# LinkLite.net
KiCad netlist of a schematic drawn in Altium Designer
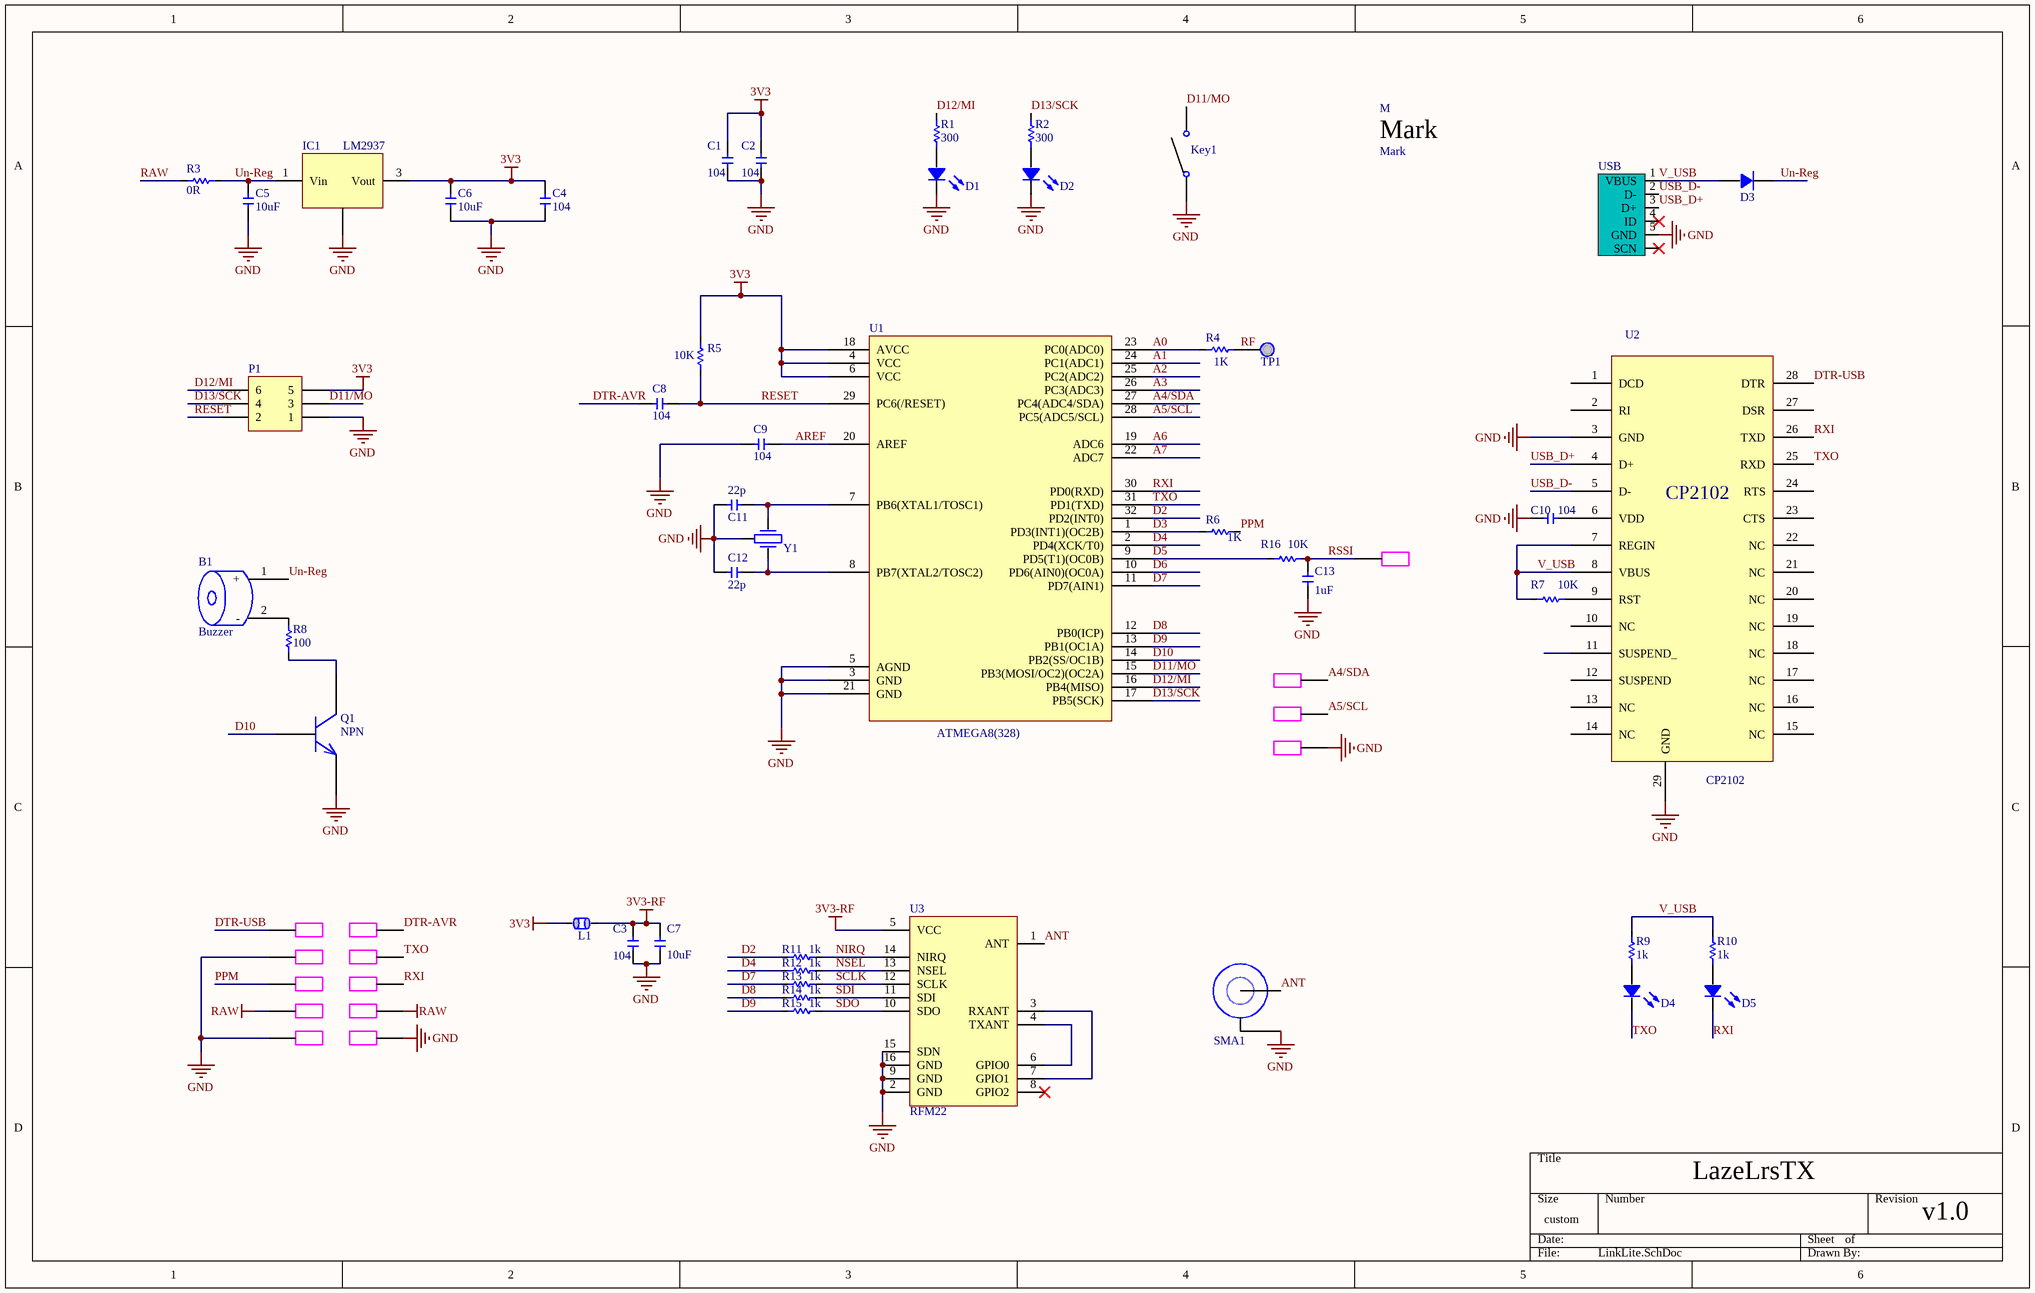
[diagram p0: LinkLite.SchDoc]

(export (version "E")
  (design (tool "Eeschema 10.0.6"))
  (components
    (comp (ref "B1") (value "Buzzer") (footprint "BUZZER9055") (libsource (lib "Drone") (part "Buzzer")))
    (comp (ref "C1")
      (value "104")
      (footprint "0603 CAP")
      (description "Capacitor")
      (fields (field (name "PUBLISHER") "Altium Limited"))
      (libsource (lib "Drone") (part "CAP"))
    )
    (comp (ref "C2")
      (value "104")
      (footprint "0603 CAP")
      (description "Capacitor")
      (fields (field (name "PUBLISHER") "Altium Limited"))
      (libsource (lib "Drone") (part "CAP"))
    )
    (comp (ref "C3")
      (value "104")
      (footprint "0603 CAP")
      (description "Capacitor")
      (fields (field (name "PUBLISHER") "Altium Limited"))
      (libsource (lib "Drone") (part "CAP"))
    )
    (comp (ref "C4")
      (value "104")
      (footprint "0603 CAP")
      (description "Capacitor")
      (fields (field (name "PUBLISHER") "Altium Limited"))
      (libsource (lib "Drone") (part "CAP"))
    )
    (comp (ref "C5")
      (value "10uF")
      (footprint "1206")
      (description "Capacitor")
      (fields (field (name "PUBLISHER") "Altium Limited"))
      (libsource (lib "Drone") (part "CAP"))
    )
    (comp (ref "C6")
      (value "10uF")
      (footprint "1206")
      (description "Capacitor")
      (fields (field (name "PUBLISHER") "Altium Limited"))
      (libsource (lib "Drone") (part "CAP"))
    )
    (comp (ref "C7")
      (value "10uF")
      (footprint "1206")
      (description "Capacitor")
      (fields (field (name "PUBLISHER") "Altium Limited"))
      (libsource (lib "Drone") (part "CAP"))
    )
    (comp (ref "C8")
      (value "104")
      (footprint "0603 CAP")
      (description "Capacitor")
      (fields (field (name "PUBLISHER") "Altium Limited"))
      (libsource (lib "Drone") (part "CAP"))
    )
    (comp (ref "C9")
      (value "104")
      (footprint "0603 CAP")
      (description "Capacitor")
      (fields (field (name "PUBLISHER") "Altium Limited"))
      (libsource (lib "Drone") (part "CAP"))
    )
    (comp (ref "C10")
      (value "104")
      (footprint "0603 CAP")
      (description "Capacitor")
      (fields (field (name "PUBLISHER") "Altium Limited"))
      (libsource (lib "Drone") (part "CAP"))
    )
    (comp (ref "C11")
      (value "22p")
      (footprint "0603 CAP")
      (description "Capacitor")
      (fields (field (name "PUBLISHER") "Altium Limited"))
      (libsource (lib "Drone") (part "CAP"))
    )
    (comp (ref "C12")
      (value "22p")
      (footprint "0603 CAP")
      (description "Capacitor")
      (fields (field (name "PUBLISHER") "Altium Limited"))
      (libsource (lib "Drone") (part "CAP"))
    )
    (comp (ref "C13")
      (value "1uF")
      (footprint "0603 CAP")
      (description "Capacitor")
      (fields (field (name "PUBLISHER") "Altium Limited"))
      (libsource (lib "Drone") (part "CAP"))
    )
    (comp (ref "D1")
      (value "LED")
      (footprint "0805 LED")
      (description "Typical RED, GREEN, YELLOW, AMBER GaAs LED")
      (fields (field (name "PUBLISHER") "Altium Limited"))
      (libsource (lib "Drone") (part "LED"))
    )
    (comp (ref "D2")
      (value "LED")
      (footprint "0805 LED")
      (description "Typical RED, GREEN, YELLOW, AMBER GaAs LED")
      (fields (field (name "PUBLISHER") "Altium Limited"))
      (libsource (lib "Drone") (part "LED"))
    )
    (comp (ref "D3") (value "Diode") (footprint "DIODE-SOD123") (libsource (lib "Drone") (part "Diode")))
    (comp (ref "D4")
      (value "LED")
      (footprint "0603 cap")
      (description "Typical RED, GREEN, YELLOW, AMBER GaAs LED")
      (fields (field (name "PUBLISHER") "Altium Limited"))
      (libsource (lib "Drone") (part "LED"))
    )
    (comp (ref "D5")
      (value "LED")
      (footprint "0603 cap")
      (description "Typical RED, GREEN, YELLOW, AMBER GaAs LED")
      (fields (field (name "PUBLISHER") "Altium Limited"))
      (libsource (lib "Drone") (part "LED"))
    )
    (comp (ref "IC1") (value "LM2937") (footprint "LM2937") (libsource (lib "Drone") (part "LM2937")))
    (comp (ref "Key1") (value "Key666") (footprint "KEY 666") (libsource (lib "Drone") (part "Key666")))
    (comp (ref "L1")
      (value "FB 300mA")
      (footprint "0603 IND")
      (description "Ferrite Bead 300mA")
      (fields (field (name "MANUFACTURER") "Generic Components"))
      (libsource (lib "Drone") (part "FerriteBead_300mA"))
    )
    (comp (ref "M") (value "Mark") (footprint "MarkPoint") (libsource (lib "Drone") (part "Mark")))
    (comp (ref "P1")
      (value "Header 3X2")
      (footprint "HDR2X3")
      (description "Header, 3-Pin, Dual row")
      (fields (field (name "PUBLISHER") "Altium Limited"))
      (libsource (lib "Miscellaneous Connectors") (part "Header 3X2"))
    )
    (comp (ref "Pad1") (value "EdgePad") (footprint "edgepad") (libsource (lib "") (part "EdgePad_1")))
    (comp (ref "Pad2") (value "EdgePad") (footprint "edgepad") (libsource (lib "Drone") (part "EdgePad")))
    (comp (ref "Pad3") (value "EdgePad") (footprint "edgepad") (libsource (lib "") (part "EdgePad_1")))
    (comp (ref "Pad4") (value "EdgePad") (footprint "edgepad") (libsource (lib "Drone") (part "EdgePad")))
    (comp (ref "Pad5") (value "EdgePad") (footprint "edgepad") (libsource (lib "") (part "EdgePad_1")))
    (comp (ref "Pad6") (value "EdgePad") (footprint "edgepad") (libsource (lib "Drone") (part "EdgePad")))
    (comp (ref "Pad7") (value "EdgePad") (footprint "edgepad") (libsource (lib "") (part "EdgePad_1")))
    (comp (ref "Pad8") (value "EdgePad") (footprint "edgepad") (libsource (lib "Drone") (part "EdgePad")))
    (comp (ref "Pad9") (value "EdgePad") (footprint "edgepad") (libsource (lib "") (part "EdgePad_1")))
    (comp (ref "Pad10") (value "EdgePad") (footprint "edgepad") (libsource (lib "Drone") (part "EdgePad")))
    (comp (ref "Pad11") (value "EdgePad") (footprint "edgepad") (libsource (lib "Drone") (part "EdgePad")))
    (comp (ref "Pad12") (value "EdgePad") (footprint "edgepad") (libsource (lib "Drone") (part "EdgePad")))
    (comp (ref "Pad13") (value "EdgePad") (footprint "edgepad") (libsource (lib "") (part "EdgePad_1")))
    (comp (ref "Pad14") (value "EdgePad") (footprint "edgepad") (libsource (lib "Drone") (part "EdgePad")))
    (comp (ref "Q1") (value "NPN") (footprint "NPN-SOT-23B_M") (libsource (lib "Drone") (part "NPN")))
    (comp (ref "R1")
      (value "300")
      (footprint "0603 RES")
      (description "Resistor")
      (fields (field (name "PUBLISHER") "Altium Limited"))
      (libsource (lib "Drone") (part "Res"))
    )
    (comp (ref "R2")
      (value "300")
      (footprint "0603 RES")
      (description "Resistor")
      (fields (field (name "PUBLISHER") "Altium Limited"))
      (libsource (lib "Drone") (part "Res"))
    )
    (comp (ref "R3")
      (value "0R")
      (footprint "0603 RES")
      (description "Resistor")
      (fields (field (name "PUBLISHER") "Altium Limited"))
      (libsource (lib "Drone") (part "Res"))
    )
    (comp (ref "R4")
      (value "1K")
      (footprint "0603 RES")
      (description "Resistor")
      (fields (field (name "PUBLISHER") "Altium Limited"))
      (libsource (lib "Drone") (part "Res"))
    )
    (comp (ref "R5")
      (value "10K")
      (footprint "0603 RES")
      (description "Resistor")
      (fields (field (name "PUBLISHER") "Altium Limited"))
      (libsource (lib "Drone") (part "Res"))
    )
    (comp (ref "R6")
      (value "1K")
      (footprint "0603 RES")
      (description "Resistor")
      (fields (field (name "PUBLISHER") "Altium Limited"))
      (libsource (lib "Drone") (part "Res"))
    )
    (comp (ref "R7")
      (value "10K")
      (footprint "0603 RES")
      (description "Resistor")
      (fields (field (name "PUBLISHER") "Altium Limited"))
      (libsource (lib "Drone") (part "Res"))
    )
    (comp (ref "R8")
      (value "100")
      (footprint "0603 RES")
      (description "Resistor")
      (fields (field (name "PUBLISHER") "Altium Limited"))
      (libsource (lib "Drone") (part "Res"))
    )
    (comp (ref "R9")
      (value "1k")
      (footprint "0603 RES")
      (description "Resistor")
      (fields (field (name "PUBLISHER") "Altium Limited"))
      (libsource (lib "Drone") (part "Res"))
    )
    (comp (ref "R10")
      (value "1k")
      (footprint "0603 RES")
      (description "Resistor")
      (fields (field (name "PUBLISHER") "Altium Limited"))
      (libsource (lib "Drone") (part "Res"))
    )
    (comp (ref "R11")
      (value "1k")
      (footprint "0603 RES")
      (description "Resistor")
      (fields (field (name "PUBLISHER") "Altium Limited"))
      (libsource (lib "Drone") (part "Res"))
    )
    (comp (ref "R12")
      (value "1k")
      (footprint "0603 RES")
      (description "Resistor")
      (fields (field (name "PUBLISHER") "Altium Limited"))
      (libsource (lib "Drone") (part "Res"))
    )
    (comp (ref "R13")
      (value "1k")
      (footprint "0603 RES")
      (description "Resistor")
      (fields (field (name "PUBLISHER") "Altium Limited"))
      (libsource (lib "Drone") (part "Res"))
    )
    (comp (ref "R14")
      (value "1k")
      (footprint "0603 RES")
      (description "Resistor")
      (fields (field (name "PUBLISHER") "Altium Limited"))
      (libsource (lib "Drone") (part "Res"))
    )
    (comp (ref "R15")
      (value "1k")
      (footprint "0603 RES")
      (description "Resistor")
      (fields (field (name "PUBLISHER") "Altium Limited"))
      (libsource (lib "Drone") (part "Res"))
    )
    (comp (ref "R16")
      (value "10K")
      (footprint "0603 RES")
      (description "Resistor")
      (fields (field (name "PUBLISHER") "Altium Limited"))
      (libsource (lib "Drone") (part "Res"))
    )
    (comp (ref "SMA1") (value "SMA Base") (footprint "ANT SMA") (libsource (lib "Drone") (part "SMA Base")))
    (comp (ref "TP1")
      (value "Test Pad")
      (footprint "Test Pad 1.2MM")
      (libsource (lib "Drone") (part "Test Pad"))
    )
    (comp (ref "U1")
      (value "ATmega328")
      (footprint "ATMEGA328FIX")
      (libsource (lib "Drone") (part "ATmega328"))
    )
    (comp (ref "U2") (value "CP2102") (footprint "CP2102") (libsource (lib "Drone") (part "CP2102")))
    (comp (ref "U3") (value "RFM22") (footprint "RFM22SMD") (libsource (lib "Drone") (part "RFM22")))
    (comp (ref "USB")
      (value "USB")
      (footprint "MINI USB A")
      (description "USB Type-B SMT Socket")
      (libsource (lib "Drone") (part "USB_SMT_B"))
    )
    (comp (ref "Y1")
      (value "Crystal3Foot")
      (footprint "Crystal3Foot")
      (libsource (lib "Drone") (part "Crystal3Foot"))
    )
  )
  (nets
    (net (code "1") (name "/A0") (class "Default")
      (node (ref "R4") (pin "2") (pinfunction "2_2") (pintype "passive"))
      (node (ref "U1") (pin "23") (pinfunction "PC0(ADC0)_23") (pintype "passive"))
    )
    (net (code "2") (name "/A1") (class "Default")
      (node (ref "U1") (pin "24") (pinfunction "PC1(ADC1)_24") (pintype "passive"))
    )
    (net (code "3") (name "/A2") (class "Default")
      (node (ref "U1") (pin "25") (pinfunction "PC2(ADC2)_25") (pintype "passive"))
    )
    (net (code "4") (name "/A3") (class "Default")
      (node (ref "U1") (pin "26") (pinfunction "PC3(ADC3)_26") (pintype "passive"))
    )
    (net (code "5") (name "/A4{slash}SDA") (class "Default")
      (node (ref "Pad10") (pin "1") (pinfunction "1_1") (pintype "passive"))
      (node (ref "U1") (pin "27") (pinfunction "PC4(ADC4/SDA)_27") (pintype "passive"))
    )
    (net (code "6") (name "/A5{slash}SCL") (class "Default")
      (node (ref "Pad11") (pin "1") (pinfunction "1_1") (pintype "passive"))
      (node (ref "U1") (pin "28") (pinfunction "PC5(ADC5/SCL)_28") (pintype "passive"))
    )
    (net (code "7") (name "/A6") (class "Default")
      (node (ref "U1") (pin "19") (pinfunction "ADC6_19") (pintype "passive"))
    )
    (net (code "8") (name "/A7") (class "Default")
      (node (ref "U1") (pin "22") (pinfunction "ADC7_22") (pintype "passive"))
    )
    (net (code "9") (name "/ANT") (class "Default")
      (node (ref "SMA1") (pin "1") (pinfunction "Ant_1") (pintype "passive"))
      (node (ref "U3") (pin "1") (pinfunction "ANT_1") (pintype "passive"))
    )
    (net (code "10") (name "/AREF") (class "Default")
      (node (ref "C9") (pin "1") (pinfunction "1_1") (pintype "passive"))
      (node (ref "U1") (pin "20") (pinfunction "AREF_20") (pintype "passive"))
    )
    (net (code "11") (name "/D2") (class "Default")
      (node (ref "R11") (pin "2") (pinfunction "2_2") (pintype "passive"))
      (node (ref "U1") (pin "32") (pinfunction "PD2(INT0)_32") (pintype "passive"))
    )
    (net (code "12") (name "/D3") (class "Default")
      (node (ref "R6") (pin "2") (pinfunction "2_2") (pintype "passive"))
      (node (ref "U1") (pin "1") (pinfunction "PD3(INT1)(OC2B)_1") (pintype "passive"))
    )
    (net (code "13") (name "/D4") (class "Default")
      (node (ref "R12") (pin "2") (pinfunction "2_2") (pintype "passive"))
      (node (ref "U1") (pin "2") (pinfunction "PD4(XCK/T0)_2") (pintype "passive"))
    )
    (net (code "14") (name "/D5") (class "Default")
      (node (ref "R16") (pin "2") (pinfunction "2_2") (pintype "passive"))
      (node (ref "U1") (pin "9") (pinfunction "PD5(T1)(OC0B)_9") (pintype "passive"))
    )
    (net (code "15") (name "/D6") (class "Default")
      (node (ref "U1") (pin "10") (pinfunction "PD6(AIN0)(OC0A)_10") (pintype "passive"))
    )
    (net (code "16") (name "/D7") (class "Default")
      (node (ref "R13") (pin "2") (pinfunction "2_2") (pintype "passive"))
      (node (ref "U1") (pin "11") (pinfunction "PD7(AIN1)_11") (pintype "passive"))
    )
    (net (code "17") (name "/D8") (class "Default")
      (node (ref "R14") (pin "2") (pinfunction "2_2") (pintype "passive"))
      (node (ref "U1") (pin "12") (pinfunction "PB0(ICP)_12") (pintype "passive"))
    )
    (net (code "18") (name "/D9") (class "Default")
      (node (ref "R15") (pin "2") (pinfunction "2_2") (pintype "passive"))
      (node (ref "U1") (pin "13") (pinfunction "PB1(OC1A)_13") (pintype "passive"))
    )
    (net (code "19") (name "/D10") (class "Default")
      (node (ref "Q1") (pin "1") (pinfunction "Sig_1") (pintype "passive"))
      (node (ref "U1") (pin "14") (pinfunction "PB2(SS/OC1B)_14") (pintype "passive"))
    )
    (net (code "20") (name "/D11{slash}MO") (class "Default")
      (node (ref "Key1") (pin "2") (pinfunction "2_2") (pintype "passive"))
      (node (ref "P1") (pin "3") (pinfunction "3_3") (pintype "passive"))
      (node (ref "U1") (pin "15") (pinfunction "PB3(MOSI/OC2)(OC2A)_15") (pintype "passive"))
    )
    (net (code "21") (name "/D12{slash}MI") (class "Default")
      (node (ref "P1") (pin "6") (pinfunction "6_6") (pintype "passive"))
      (node (ref "R1") (pin "1") (pinfunction "1_1") (pintype "passive"))
      (node (ref "U1") (pin "16") (pinfunction "PB4(MISO)_16") (pintype "passive"))
    )
    (net (code "22") (name "/D13{slash}SCK") (class "Default")
      (node (ref "P1") (pin "4") (pinfunction "4_4") (pintype "passive"))
      (node (ref "R2") (pin "1") (pinfunction "1_1") (pintype "passive"))
      (node (ref "U1") (pin "17") (pinfunction "PB5(SCK)_17") (pintype "passive"))
    )
    (net (code "23") (name "/DTR-AVR") (class "Default")
      (node (ref "C8") (pin "2") (pinfunction "2_2") (pintype "passive"))
      (node (ref "Pad2") (pin "1") (pinfunction "1_1") (pintype "passive"))
    )
    (net (code "24") (name "/DTR-USB") (class "Default")
      (node (ref "Pad1") (pin "1") (pinfunction "1_1") (pintype "passive"))
      (node (ref "U2") (pin "28") (pinfunction "DTR_28") (pintype "passive"))
    )
    (net (code "25") (name "/NIRQ") (class "Default")
      (node (ref "R11") (pin "1") (pinfunction "1_1") (pintype "passive"))
      (node (ref "U3") (pin "14") (pinfunction "NIRQ_14") (pintype "passive"))
    )
    (net (code "26") (name "/NSEL") (class "Default")
      (node (ref "R12") (pin "1") (pinfunction "1_1") (pintype "passive"))
      (node (ref "U3") (pin "13") (pinfunction "NSEL_13") (pintype "passive"))
    )
    (net (code "27") (name "/PPM") (class "Default")
      (node (ref "Pad5") (pin "1") (pinfunction "1_1") (pintype "passive"))
      (node (ref "R6") (pin "1") (pinfunction "1_1") (pintype "passive"))
    )
    (net (code "28") (name "/RESET") (class "Default")
      (node (ref "C8") (pin "1") (pinfunction "1_1") (pintype "passive"))
      (node (ref "P1") (pin "2") (pinfunction "2_2") (pintype "passive"))
      (node (ref "R5") (pin "1") (pinfunction "1_1") (pintype "passive"))
      (node (ref "U1") (pin "29") (pinfunction "PC6(/RESET)_29") (pintype "passive"))
    )
    (net (code "29") (name "/RF") (class "Default")
      (node (ref "R4") (pin "1") (pinfunction "1_1") (pintype "passive"))
      (node (ref "TP1") (pin "1") (pinfunction "1_1") (pintype "passive"))
    )
    (net (code "30") (name "/RSSI") (class "Default")
      (node (ref "C13") (pin "2") (pinfunction "2_2") (pintype "passive"))
      (node (ref "Pad13") (pin "1") (pinfunction "1_1") (pintype "passive"))
      (node (ref "R16") (pin "1") (pinfunction "1_1") (pintype "passive"))
    )
    (net (code "31") (name "/RXI") (class "Default")
      (node (ref "D5") (pin "2") (pinfunction "K_2") (pintype "passive"))
      (node (ref "Pad6") (pin "1") (pinfunction "1_1") (pintype "passive"))
      (node (ref "U1") (pin "30") (pinfunction "PD0(RXD)_30") (pintype "passive"))
      (node (ref "U2") (pin "26") (pinfunction "TXD_26") (pintype "passive"))
    )
    (net (code "32") (name "/SCLK") (class "Default")
      (node (ref "R13") (pin "1") (pinfunction "1_1") (pintype "passive"))
      (node (ref "U3") (pin "12") (pinfunction "SCLK_12") (pintype "passive"))
    )
    (net (code "33") (name "/SDI") (class "Default")
      (node (ref "R14") (pin "1") (pinfunction "1_1") (pintype "passive"))
      (node (ref "U3") (pin "11") (pinfunction "SDI_11") (pintype "passive"))
    )
    (net (code "34") (name "/SDO") (class "Default")
      (node (ref "R15") (pin "1") (pinfunction "1_1") (pintype "passive"))
      (node (ref "U3") (pin "10") (pinfunction "SDO_10") (pintype "passive"))
    )
    (net (code "35") (name "/TXO") (class "Default")
      (node (ref "D4") (pin "2") (pinfunction "K_2") (pintype "passive"))
      (node (ref "Pad4") (pin "1") (pinfunction "1_1") (pintype "passive"))
      (node (ref "U1") (pin "31") (pinfunction "PD1(TXD)_31") (pintype "passive"))
      (node (ref "U2") (pin "25") (pinfunction "RXD_25") (pintype "passive"))
    )
    (net (code "36") (name "/USB_D+") (class "Default")
      (node (ref "U2") (pin "4") (pinfunction "D+_4") (pintype "passive"))
      (node (ref "USB") (pin "3") (pinfunction "D+_3") (pintype "passive"))
    )
    (net (code "37") (name "/USB_D-") (class "Default")
      (node (ref "U2") (pin "5") (pinfunction "D-_5") (pintype "passive"))
      (node (ref "USB") (pin "2") (pinfunction "D-_2") (pintype "passive"))
    )
    (net (code "38") (name "/Un-Reg") (class "Default")
      (node (ref "B1") (pin "1") (pinfunction "+_1") (pintype "passive"))
      (node (ref "C5") (pin "2") (pinfunction "2_2") (pintype "passive"))
      (node (ref "D3") (pin "2") (pinfunction "B_2") (pintype "passive"))
      (node (ref "IC1") (pin "1") (pinfunction "Vin_1") (pintype "passive"))
      (node (ref "R3") (pin "1") (pinfunction "1_1") (pintype "passive"))
    )
    (net (code "39") (name "/V_USB") (class "Default")
      (node (ref "D3") (pin "1") (pinfunction "A_1") (pintype "passive"))
      (node (ref "R10") (pin "1") (pinfunction "1_1") (pintype "passive"))
      (node (ref "R7") (pin "2") (pinfunction "2_2") (pintype "passive"))
      (node (ref "R9") (pin "1") (pinfunction "1_1") (pintype "passive"))
      (node (ref "U2") (pin "7") (pinfunction "REGIN_7") (pintype "passive"))
      (node (ref "U2") (pin "8") (pinfunction "VBUS_8") (pintype "passive"))
      (node (ref "USB") (pin "1") (pinfunction "VBUS_1") (pintype "passive"))
    )
    (net (code "40") (name "3V3") (class "Default")
      (node (ref "C1") (pin "1") (pinfunction "1_1") (pintype "passive"))
      (node (ref "C2") (pin "1") (pinfunction "1_1") (pintype "passive"))
      (node (ref "C4") (pin "1") (pinfunction "1_1") (pintype "passive"))
      (node (ref "C6") (pin "2") (pinfunction "2_2") (pintype "passive"))
      (node (ref "IC1") (pin "3") (pinfunction "Vout_3") (pintype "passive"))
      (node (ref "L1") (pin "1") (pinfunction "1_1") (pintype "passive"))
      (node (ref "P1") (pin "5") (pinfunction "5_5") (pintype "passive"))
      (node (ref "R5") (pin "2") (pinfunction "2_2") (pintype "passive"))
      (node (ref "U1") (pin "18") (pinfunction "AVCC_18") (pintype "passive"))
      (node (ref "U1") (pin "4") (pinfunction "VCC_4") (pintype "passive"))
      (node (ref "U1") (pin "6") (pinfunction "VCC_6") (pintype "passive"))
    )
    (net (code "41") (name "3V3-RF") (class "Default")
      (node (ref "C3") (pin "1") (pinfunction "1_1") (pintype "passive"))
      (node (ref "C7") (pin "1") (pinfunction "1_1") (pintype "passive"))
      (node (ref "L1") (pin "2") (pinfunction "2_2") (pintype "passive"))
      (node (ref "U3") (pin "5") (pinfunction "VCC_5") (pintype "passive"))
    )
    (net (code "42") (name "GND") (class "Default")
      (node (ref "C1") (pin "2") (pinfunction "2_2") (pintype "passive"))
      (node (ref "C10") (pin "1") (pinfunction "1_1") (pintype "passive"))
      (node (ref "C11") (pin "1") (pinfunction "1_1") (pintype "passive"))
      (node (ref "C12") (pin "1") (pinfunction "1_1") (pintype "passive"))
      (node (ref "C13") (pin "1") (pinfunction "1_1") (pintype "passive"))
      (node (ref "C2") (pin "2") (pinfunction "2_2") (pintype "passive"))
      (node (ref "C3") (pin "2") (pinfunction "2_2") (pintype "passive"))
      (node (ref "C4") (pin "2") (pinfunction "2_2") (pintype "passive"))
      (node (ref "C5") (pin "1") (pinfunction "1_1") (pintype "passive"))
      (node (ref "C6") (pin "1") (pinfunction "1_1") (pintype "passive"))
      (node (ref "C7") (pin "2") (pinfunction "2_2") (pintype "passive"))
      (node (ref "C9") (pin "2") (pinfunction "2_2") (pintype "passive"))
      (node (ref "D1") (pin "2") (pinfunction "K_2") (pintype "passive"))
      (node (ref "D2") (pin "2") (pinfunction "K_2") (pintype "passive"))
      (node (ref "IC1") (pin "2") (pinfunction "Gnd_2") (pintype "passive"))
      (node (ref "Key1") (pin "1") (pinfunction "1_1") (pintype "passive"))
      (node (ref "P1") (pin "1") (pinfunction "1_1") (pintype "passive"))
      (node (ref "Pad12") (pin "1") (pinfunction "1_1") (pintype "passive"))
      (node (ref "Pad14") (pin "1") (pinfunction "1_1") (pintype "passive"))
      (node (ref "Pad3") (pin "1") (pinfunction "1_1") (pintype "passive"))
      (node (ref "Pad9") (pin "1") (pinfunction "1_1") (pintype "passive"))
      (node (ref "Q1") (pin "2") (pinfunction "Gnd_2") (pintype "passive"))
      (node (ref "SMA1") (pin "2") (pinfunction "Gnd_2") (pintype "passive"))
      (node (ref "U1") (pin "21") (pinfunction "GND_21") (pintype "passive"))
      (node (ref "U1") (pin "3") (pinfunction "GND_3") (pintype "passive"))
      (node (ref "U1") (pin "5") (pinfunction "AGND_5") (pintype "passive"))
      (node (ref "U2") (pin "29") (pinfunction "GND_29") (pintype "passive"))
      (node (ref "U2") (pin "3") (pinfunction "GND_3") (pintype "passive"))
      (node (ref "U3") (pin "15") (pinfunction "SDN_15") (pintype "passive"))
      (node (ref "U3") (pin "16") (pinfunction "GND_16") (pintype "passive"))
      (node (ref "U3") (pin "2") (pinfunction "GND_2") (pintype "passive"))
      (node (ref "U3") (pin "9") (pinfunction "GND_9") (pintype "passive"))
      (node (ref "USB") (pin "5") (pinfunction "GND_5") (pintype "passive"))
      (node (ref "Y1") (pin "2") (pinfunction "2_2") (pintype "passive"))
    )
    (net (code "43") (name "Net-(B1--)") (class "Default")
      (node (ref "B1") (pin "2") (pinfunction "-_2") (pintype "passive"))
      (node (ref "R8") (pin "1") (pinfunction "1_1") (pintype "passive"))
    )
    (net (code "44") (name "Net-(D1-A)") (class "Default")
      (node (ref "D1") (pin "1") (pinfunction "A_1") (pintype "passive"))
      (node (ref "R1") (pin "2") (pinfunction "2_2") (pintype "passive"))
    )
    (net (code "45") (name "Net-(D2-A)") (class "Default")
      (node (ref "D2") (pin "1") (pinfunction "A_1") (pintype "passive"))
      (node (ref "R2") (pin "2") (pinfunction "2_2") (pintype "passive"))
    )
    (net (code "46") (name "Net-(D4-A)") (class "Default")
      (node (ref "D4") (pin "1") (pinfunction "A_1") (pintype "passive"))
      (node (ref "R9") (pin "2") (pinfunction "2_2") (pintype "passive"))
    )
    (net (code "47") (name "Net-(D5-A)") (class "Default")
      (node (ref "D5") (pin "1") (pinfunction "A_1") (pintype "passive"))
      (node (ref "R10") (pin "2") (pinfunction "2_2") (pintype "passive"))
    )
    (net (code "48") (name "Net-(Q1-Collector)") (class "Default")
      (node (ref "Q1") (pin "3") (pinfunction "Collector_3") (pintype "passive"))
      (node (ref "R8") (pin "2") (pinfunction "2_2") (pintype "passive"))
    )
    (net (code "49") (name "Net-(U1-PB6(XTAL1{slash}TOSC1))") (class "Default")
      (node (ref "C11") (pin "2") (pinfunction "2_2") (pintype "passive"))
      (node (ref "U1") (pin "7") (pinfunction "PB6(XTAL1/TOSC1)_7") (pintype "passive"))
      (node (ref "Y1") (pin "1") (pinfunction "0_1") (pintype "passive"))
    )
    (net (code "50") (name "Net-(U1-PB7(XTAL2{slash}TOSC2))") (class "Default")
      (node (ref "C12") (pin "2") (pinfunction "2_2") (pintype "passive"))
      (node (ref "U1") (pin "8") (pinfunction "PB7(XTAL2/TOSC2)_8") (pintype "passive"))
      (node (ref "Y1") (pin "3") (pinfunction "1_3") (pintype "passive"))
    )
    (net (code "51") (name "Net-(U2-RST)") (class "Default")
      (node (ref "R7") (pin "1") (pinfunction "1_1") (pintype "passive"))
      (node (ref "U2") (pin "9") (pinfunction "RST_9") (pintype "passive"))
    )
    (net (code "52") (name "Net-(U2-VDD)") (class "Default")
      (node (ref "C10") (pin "2") (pinfunction "2_2") (pintype "passive"))
      (node (ref "U2") (pin "6") (pinfunction "VDD_6") (pintype "passive"))
    )
    (net (code "53") (name "Net-(U3-GPIO0)") (class "Default")
      (node (ref "U3") (pin "4") (pinfunction "TXANT_4") (pintype "passive"))
      (node (ref "U3") (pin "6") (pinfunction "GPIO0_6") (pintype "passive"))
    )
    (net (code "54") (name "Net-(U3-GPIO1)") (class "Default")
      (node (ref "U3") (pin "3") (pinfunction "RXANT_3") (pintype "passive"))
      (node (ref "U3") (pin "7") (pinfunction "GPIO1_7") (pintype "passive"))
    )
    (net (code "55") (name "RAW") (class "Default")
      (node (ref "Pad7") (pin "1") (pinfunction "1_1") (pintype "passive"))
      (node (ref "Pad8") (pin "1") (pinfunction "1_1") (pintype "passive"))
      (node (ref "R3") (pin "2") (pinfunction "2_2") (pintype "passive"))
    )
    (net (code "56") (name "unconnected-(U2-CTS-Pad23)") (class "Default")
      (node (ref "U2") (pin "23") (pinfunction "CTS_23") (pintype "passive"))
    )
    (net (code "57") (name "unconnected-(U2-DCD-Pad1)") (class "Default")
      (node (ref "U2") (pin "1") (pinfunction "DCD_1") (pintype "passive"))
    )
    (net (code "58") (name "unconnected-(U2-DSR-Pad27)") (class "Default")
      (node (ref "U2") (pin "27") (pinfunction "DSR_27") (pintype "passive"))
    )
    (net (code "59") (name "unconnected-(U2-NC-Pad10)") (class "Default")
      (node (ref "U2") (pin "10") (pinfunction "NC_10") (pintype "passive"))
    )
    (net (code "60") (name "unconnected-(U2-NC-Pad13)") (class "Default")
      (node (ref "U2") (pin "13") (pinfunction "NC_13") (pintype "passive"))
    )
    (net (code "61") (name "unconnected-(U2-NC-Pad14)") (class "Default")
      (node (ref "U2") (pin "14") (pinfunction "NC_14") (pintype "passive"))
    )
    (net (code "62") (name "unconnected-(U2-NC-Pad15)") (class "Default")
      (node (ref "U2") (pin "15") (pinfunction "NC_15") (pintype "passive"))
    )
    (net (code "63") (name "unconnected-(U2-NC-Pad16)") (class "Default")
      (node (ref "U2") (pin "16") (pinfunction "NC_16") (pintype "passive"))
    )
    (net (code "64") (name "unconnected-(U2-NC-Pad17)") (class "Default")
      (node (ref "U2") (pin "17") (pinfunction "NC_17") (pintype "passive"))
    )
    (net (code "65") (name "unconnected-(U2-NC-Pad18)") (class "Default")
      (node (ref "U2") (pin "18") (pinfunction "NC_18") (pintype "passive"))
    )
    (net (code "66") (name "unconnected-(U2-NC-Pad19)") (class "Default")
      (node (ref "U2") (pin "19") (pinfunction "NC_19") (pintype "passive"))
    )
    (net (code "67") (name "unconnected-(U2-NC-Pad20)") (class "Default")
      (node (ref "U2") (pin "20") (pinfunction "NC_20") (pintype "passive"))
    )
    (net (code "68") (name "unconnected-(U2-NC-Pad21)") (class "Default")
      (node (ref "U2") (pin "21") (pinfunction "NC_21") (pintype "passive"))
    )
    (net (code "69") (name "unconnected-(U2-NC-Pad22)") (class "Default")
      (node (ref "U2") (pin "22") (pinfunction "NC_22") (pintype "passive"))
    )
    (net (code "70") (name "unconnected-(U2-RI-Pad2)") (class "Default")
      (node (ref "U2") (pin "2") (pinfunction "RI_2") (pintype "passive"))
    )
    (net (code "71") (name "unconnected-(U2-RTS-Pad24)") (class "Default")
      (node (ref "U2") (pin "24") (pinfunction "RTS_24") (pintype "passive"))
    )
    (net (code "72") (name "unconnected-(U2-SUSPEND-Pad12)") (class "Default")
      (node (ref "U2") (pin "12") (pinfunction "SUSPEND_12") (pintype "passive"))
    )
    (net (code "73") (name "unconnected-(U2-SUSPEND_-Pad11)") (class "Default")
      (node (ref "U2") (pin "11") (pinfunction "SUSPEND__11") (pintype "passive"))
    )
    (net (code "74") (name "unconnected-(U3-GPIO2-Pad8)") (class "Default")
      (node (ref "U3") (pin "8") (pinfunction "GPIO2_8") (pintype "passive+no_connect"))
    )
    (net (code "75") (name "unconnected-(USB-ID-Pad4)") (class "Default")
      (node (ref "USB") (pin "4") (pinfunction "ID_4") (pintype "passive+no_connect"))
    )
    (net (code "76") (name "unconnected-(USB-SCN-Pad0)") (class "Default")
      (node (ref "USB") (pin "0") (pinfunction "SCN_0") (pintype "passive+no_connect"))
    )
  )
)
